# eMMC_TPM.net
KiCad netlist of a schematic drawn in Altium Designer
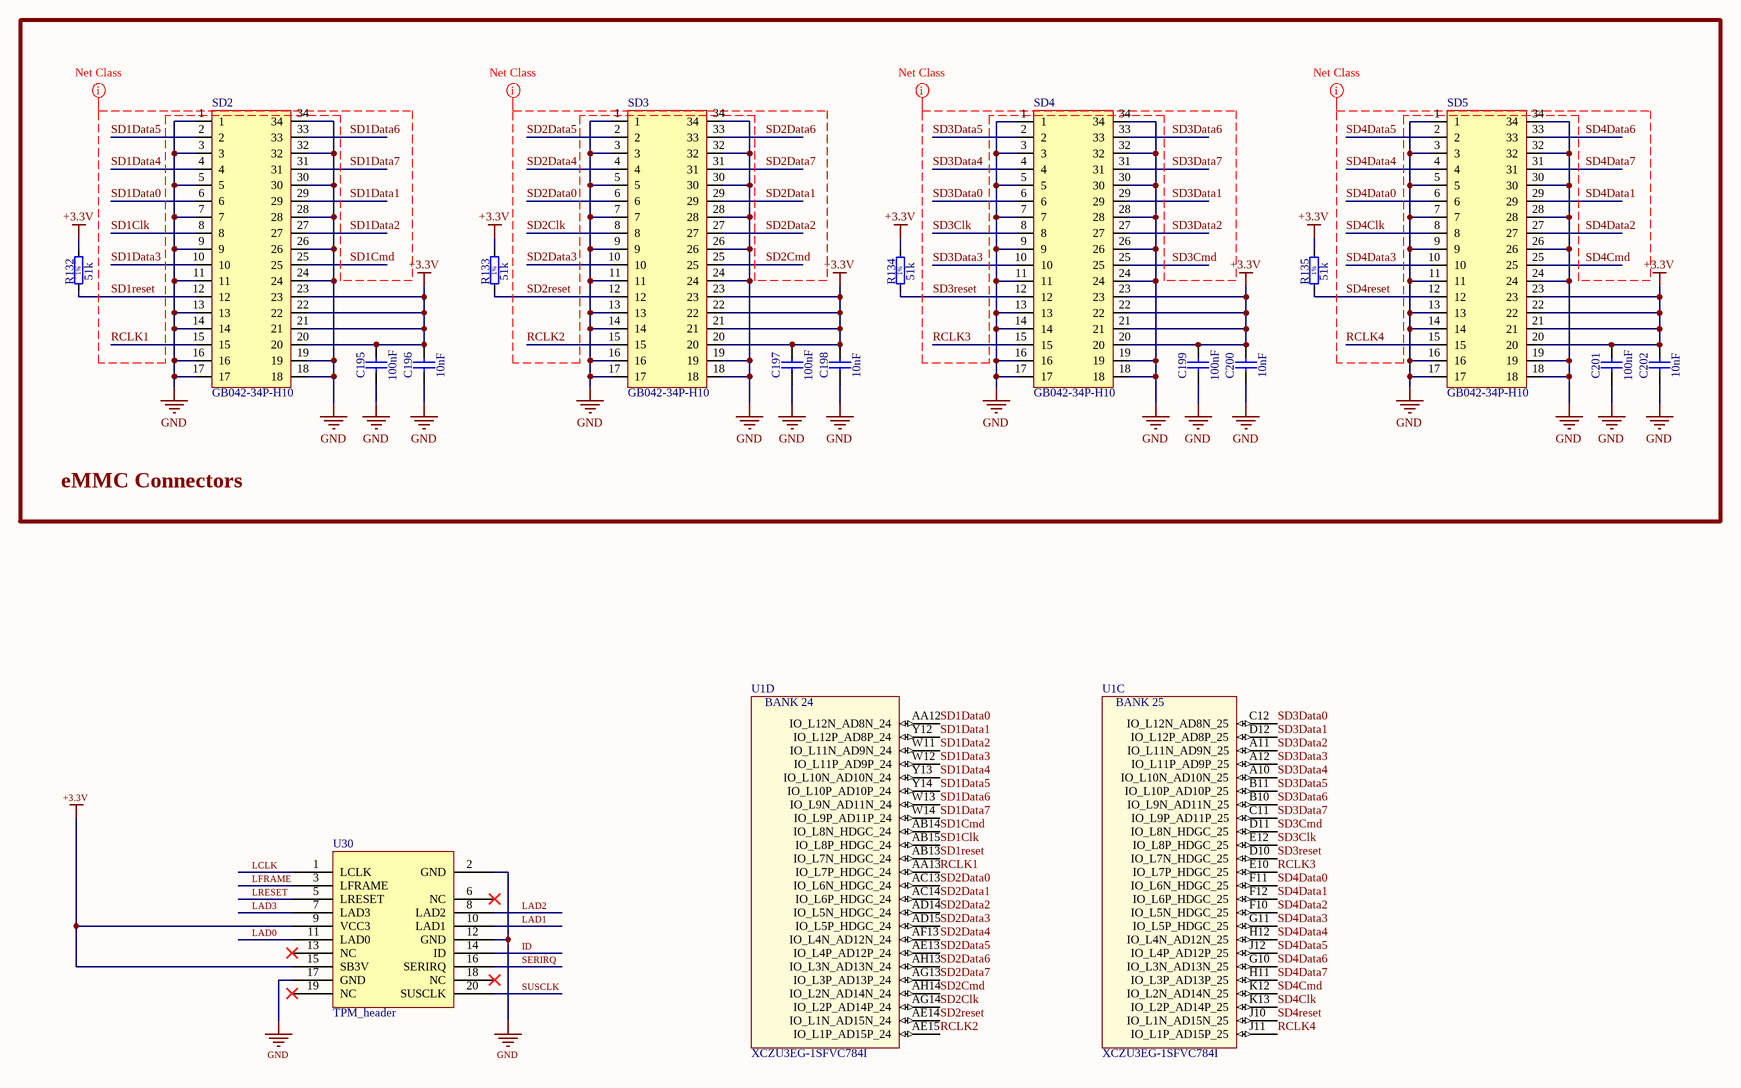
[diagram p0: eMMC_TPM.SchDoc]

(export (version "E")
  (design (tool "Eeschema 10.0.6"))
  (components
    (comp (ref "C195")
      (value "100nF")
      (footprint "Ultrascale_PcbLib:CAPC1608X87N")
      (description "Non-polarised capacitor")
      (fields
        (field (name "PART NUMBER") "CC0603_100NF_50V_10%_X7R")
        (field (name "VOLTAGE") "50V")
        (field (name "AUTHOR") "CERN DEM JLC")
      )
      (libsource (lib "Ultrascale_SchLib") (part "Capacitor - non polarized"))
    )
    (comp (ref "C196")
      (value "10nF")
      (footprint "Ultrascale_PcbLib:CAPC1608X87N")
      (description "Non-polarised capacitor")
      (fields
        (field (name "PART NUMBER") "CC0603_10NF_50V_10%_X7R")
        (field (name "VOLTAGE") "50V")
        (field (name "AUTHOR") "CERN DEM JLC")
      )
      (libsource (lib "Ultrascale_SchLib") (part "Capacitor - non polarized"))
    )
    (comp (ref "C197")
      (value "100nF")
      (footprint "Ultrascale_PcbLib:CAPC1608X87N")
      (description "Non-polarised capacitor")
      (fields
        (field (name "PART NUMBER") "CC0603_100NF_50V_10%_X7R")
        (field (name "VOLTAGE") "50V")
        (field (name "AUTHOR") "CERN DEM JLC")
      )
      (libsource (lib "Ultrascale_SchLib") (part "Capacitor - non polarized"))
    )
    (comp (ref "C198")
      (value "10nF")
      (footprint "Ultrascale_PcbLib:CAPC1608X87N")
      (description "Non-polarised capacitor")
      (fields
        (field (name "PART NUMBER") "CC0603_10NF_50V_10%_X7R")
        (field (name "VOLTAGE") "50V")
        (field (name "AUTHOR") "CERN DEM JLC")
      )
      (libsource (lib "Ultrascale_SchLib") (part "Capacitor - non polarized"))
    )
    (comp (ref "C199")
      (value "100nF")
      (footprint "Ultrascale_PcbLib:CAPC1608X87N")
      (description "Non-polarised capacitor")
      (fields
        (field (name "PART NUMBER") "CC0603_100NF_50V_10%_X7R")
        (field (name "VOLTAGE") "50V")
        (field (name "AUTHOR") "CERN DEM JLC")
      )
      (libsource (lib "Ultrascale_SchLib") (part "Capacitor - non polarized"))
    )
    (comp (ref "C200")
      (value "10nF")
      (footprint "Ultrascale_PcbLib:CAPC1608X87N")
      (description "Non-polarised capacitor")
      (fields
        (field (name "PART NUMBER") "CC0603_10NF_50V_10%_X7R")
        (field (name "VOLTAGE") "50V")
        (field (name "AUTHOR") "CERN DEM JLC")
      )
      (libsource (lib "Ultrascale_SchLib") (part "Capacitor - non polarized"))
    )
    (comp (ref "C201")
      (value "100nF")
      (footprint "Ultrascale_PcbLib:CAPC1608X87N")
      (description "Non-polarised capacitor")
      (fields
        (field (name "PART NUMBER") "CC0603_100NF_50V_10%_X7R")
        (field (name "VOLTAGE") "50V")
        (field (name "AUTHOR") "CERN DEM JLC")
      )
      (libsource (lib "Ultrascale_SchLib") (part "Capacitor - non polarized"))
    )
    (comp (ref "C202")
      (value "10nF")
      (footprint "Ultrascale_PcbLib:CAPC1608X87N")
      (description "Non-polarised capacitor")
      (fields
        (field (name "PART NUMBER") "CC0603_10NF_50V_10%_X7R")
        (field (name "VOLTAGE") "50V")
        (field (name "AUTHOR") "CERN DEM JLC")
      )
      (libsource (lib "Ultrascale_SchLib") (part "Capacitor - non polarized"))
    )
    (comp (ref "R132")
      (value "51k")
      (footprint "Ultrascale_PcbLib:RESC1608X55N")
      (description "Resistor - 1%")
      (fields
        (field (name "PART NUMBER") "R0603_51K_1%_0.1W_100PPM")
        (field (name "POWER") "0.1W")
        (field (name "AUTHOR") "CERN DEM JLC")
      )
      (libsource (lib "Ultrascale_SchLib") (part "Resistor - 1%"))
    )
    (comp (ref "R133")
      (value "51k")
      (footprint "Ultrascale_PcbLib:RESC1608X55N")
      (description "Resistor - 1%")
      (fields
        (field (name "PART NUMBER") "R0603_51K_1%_0.1W_100PPM")
        (field (name "POWER") "0.1W")
        (field (name "AUTHOR") "CERN DEM JLC")
      )
      (libsource (lib "Ultrascale_SchLib") (part "Resistor - 1%"))
    )
    (comp (ref "R134")
      (value "51k")
      (footprint "Ultrascale_PcbLib:RESC1608X55N")
      (description "Resistor - 1%")
      (fields
        (field (name "PART NUMBER") "R0603_51K_1%_0.1W_100PPM")
        (field (name "POWER") "0.1W")
        (field (name "AUTHOR") "CERN DEM JLC")
      )
      (libsource (lib "Ultrascale_SchLib") (part "Resistor - 1%"))
    )
    (comp (ref "R135")
      (value "51k")
      (footprint "Ultrascale_PcbLib:RESC1608X55N")
      (description "Resistor - 1%")
      (fields
        (field (name "PART NUMBER") "R0603_51K_1%_0.1W_100PPM")
        (field (name "POWER") "0.1W")
        (field (name "AUTHOR") "CERN DEM JLC")
      )
      (libsource (lib "Ultrascale_SchLib") (part "Resistor - 1%"))
    )
    (comp (ref "SD2")
      (value "GB042-34P-H10")
      (footprint "Ultrascale_PcbLib:GB042-34P-H10")
      (description "Connector, eMMC")
      (libsource (lib "Ultrascale_SchLib") (part "GB042-34P-H10"))
    )
    (comp (ref "SD3")
      (value "GB042-34P-H10")
      (footprint "Ultrascale_PcbLib:GB042-34P-H10")
      (description "Connector, eMMC")
      (libsource (lib "Ultrascale_SchLib") (part "GB042-34P-H10"))
    )
    (comp (ref "SD4")
      (value "GB042-34P-H10")
      (footprint "Ultrascale_PcbLib:GB042-34P-H10")
      (description "Connector, eMMC")
      (libsource (lib "Ultrascale_SchLib") (part "GB042-34P-H10"))
    )
    (comp (ref "SD5")
      (value "GB042-34P-H10")
      (footprint "Ultrascale_PcbLib:GB042-34P-H10")
      (description "Connector, eMMC")
      (libsource (lib "Ultrascale_SchLib") (part "GB042-34P-H10"))
    )
    (comp (ref "U1")
      (value "XCZU3EG-1SFVC784I")
      (footprint "BGA784x28")
      (description "IC FPGA 252 I/O 784FCBGA - XILINX ZYNQ ULTRASCALE+")
      (libsource (lib "Ultrascale_SchLib") (part "XCZU3EG-1SFVC784I"))
    )
    (comp (ref "U30")
      (value "TPM_header")
      (footprint "PIN HEADER 20POS")
      (description "GC-TPM-rev-20")
      (libsource (lib "Ultrascale_SchLib") (part "TPM_header"))
    )
  )
  (nets
    (net (code "1") (name "+3.3V") (class "Default")
      (node (ref "C195") (pin "2") (pinfunction "2_2") (pintype "passive"))
      (node (ref "C196") (pin "2") (pinfunction "2_2") (pintype "passive"))
      (node (ref "C197") (pin "2") (pinfunction "2_2") (pintype "passive"))
      (node (ref "C198") (pin "2") (pinfunction "2_2") (pintype "passive"))
      (node (ref "C199") (pin "2") (pinfunction "2_2") (pintype "passive"))
      (node (ref "C200") (pin "2") (pinfunction "2_2") (pintype "passive"))
      (node (ref "C201") (pin "2") (pinfunction "2_2") (pintype "passive"))
      (node (ref "C202") (pin "2") (pinfunction "2_2") (pintype "passive"))
      (node (ref "R132") (pin "2") (pinfunction "2_2") (pintype "passive"))
      (node (ref "R133") (pin "2") (pinfunction "2_2") (pintype "passive"))
      (node (ref "R134") (pin "2") (pinfunction "2_2") (pintype "passive"))
      (node (ref "R135") (pin "2") (pinfunction "2_2") (pintype "passive"))
      (node (ref "SD2") (pin "20") (pinfunction "20_20") (pintype "passive"))
      (node (ref "SD2") (pin "21") (pinfunction "21_21") (pintype "passive"))
      (node (ref "SD2") (pin "22") (pinfunction "22_22") (pintype "passive"))
      (node (ref "SD2") (pin "23") (pinfunction "23_23") (pintype "passive"))
      (node (ref "SD3") (pin "20") (pinfunction "20_20") (pintype "passive"))
      (node (ref "SD3") (pin "21") (pinfunction "21_21") (pintype "passive"))
      (node (ref "SD3") (pin "22") (pinfunction "22_22") (pintype "passive"))
      (node (ref "SD3") (pin "23") (pinfunction "23_23") (pintype "passive"))
      (node (ref "SD4") (pin "20") (pinfunction "20_20") (pintype "passive"))
      (node (ref "SD4") (pin "21") (pinfunction "21_21") (pintype "passive"))
      (node (ref "SD4") (pin "22") (pinfunction "22_22") (pintype "passive"))
      (node (ref "SD4") (pin "23") (pinfunction "23_23") (pintype "passive"))
      (node (ref "SD5") (pin "20") (pinfunction "20_20") (pintype "passive"))
      (node (ref "SD5") (pin "21") (pinfunction "21_21") (pintype "passive"))
      (node (ref "SD5") (pin "22") (pinfunction "22_22") (pintype "passive"))
      (node (ref "SD5") (pin "23") (pinfunction "23_23") (pintype "passive"))
      (node (ref "U30") (pin "15") (pinfunction "SB3V_15") (pintype "power_in"))
      (node (ref "U30") (pin "9") (pinfunction "VCC3_9") (pintype "power_in"))
    )
    (net (code "2") (name "/ID") (class "Default")
      (node (ref "U30") (pin "14") (pinfunction "ID_14") (pintype "power_in"))
    )
    (net (code "3") (name "/LAD0") (class "Default")
      (node (ref "U30") (pin "11") (pinfunction "LAD0_11") (pintype "power_in"))
    )
    (net (code "4") (name "/LAD1") (class "Default")
      (node (ref "U30") (pin "10") (pinfunction "LAD1_10") (pintype "power_in"))
    )
    (net (code "5") (name "/LAD2") (class "Default")
      (node (ref "U30") (pin "8") (pinfunction "LAD2_8") (pintype "power_in"))
    )
    (net (code "6") (name "/LAD3") (class "Default")
      (node (ref "U30") (pin "7") (pinfunction "LAD3_7") (pintype "power_in"))
    )
    (net (code "7") (name "/LCLK") (class "Default")
      (node (ref "U30") (pin "1") (pinfunction "LCLK_1") (pintype "power_in"))
    )
    (net (code "8") (name "/LFRAME") (class "Default")
      (node (ref "U30") (pin "3") (pinfunction "LFRAME_3") (pintype "power_in"))
    )
    (net (code "9") (name "/LRESET") (class "Default")
      (node (ref "U30") (pin "5") (pinfunction "LRESET_5") (pintype "power_in"))
    )
    (net (code "10") (name "/RCLK1") (class "Default")
      (node (ref "SD2") (pin "15") (pinfunction "15_15") (pintype "passive"))
      (node (ref "U1") (pin "AA13") (pinfunction "IO_L7P_HDGC_24_AA13") (pintype "bidirectional"))
    )
    (net (code "11") (name "/RCLK2") (class "Default")
      (node (ref "SD3") (pin "15") (pinfunction "15_15") (pintype "passive"))
      (node (ref "U1") (pin "AE15") (pinfunction "IO_L1P_AD15P_24_AE15") (pintype "bidirectional"))
    )
    (net (code "12") (name "/RCLK3") (class "Default")
      (node (ref "SD4") (pin "15") (pinfunction "15_15") (pintype "passive"))
      (node (ref "U1") (pin "E10") (pinfunction "IO_L7P_HDGC_25_E10") (pintype "bidirectional"))
    )
    (net (code "13") (name "/RCLK4") (class "Default")
      (node (ref "SD5") (pin "15") (pinfunction "15_15") (pintype "passive"))
      (node (ref "U1") (pin "J11") (pinfunction "IO_L1P_AD15P_25_J11") (pintype "bidirectional"))
    )
    (net (code "14") (name "/SD1Clk") (class "Default")
      (node (ref "SD2") (pin "8") (pinfunction "8_8") (pintype "passive"))
      (node (ref "U1") (pin "AB15") (pinfunction "IO_L8P_HDGC_24_AB15") (pintype "bidirectional"))
    )
    (net (code "15") (name "/SD1Cmd") (class "Default")
      (node (ref "SD2") (pin "25") (pinfunction "25_25") (pintype "passive"))
      (node (ref "U1") (pin "AB14") (pinfunction "IO_L8N_HDGC_24_AB14") (pintype "bidirectional"))
    )
    (net (code "16") (name "/SD1Data0") (class "Default")
      (node (ref "SD2") (pin "6") (pinfunction "6_6") (pintype "passive"))
      (node (ref "U1") (pin "AA12") (pinfunction "IO_L12N_AD8N_24_AA12") (pintype "bidirectional"))
    )
    (net (code "17") (name "/SD1Data1") (class "Default")
      (node (ref "SD2") (pin "29") (pinfunction "29_29") (pintype "passive"))
      (node (ref "U1") (pin "Y12") (pinfunction "IO_L12P_AD8P_24_Y12") (pintype "bidirectional"))
    )
    (net (code "18") (name "/SD1Data2") (class "Default")
      (node (ref "SD2") (pin "27") (pinfunction "27_27") (pintype "passive"))
      (node (ref "U1") (pin "W11") (pinfunction "IO_L11N_AD9N_24_W11") (pintype "bidirectional"))
    )
    (net (code "19") (name "/SD1Data3") (class "Default")
      (node (ref "SD2") (pin "10") (pinfunction "10_10") (pintype "passive"))
      (node (ref "U1") (pin "W12") (pinfunction "IO_L11P_AD9P_24_W12") (pintype "bidirectional"))
    )
    (net (code "20") (name "/SD1Data4") (class "Default")
      (node (ref "SD2") (pin "4") (pinfunction "4_4") (pintype "passive"))
      (node (ref "U1") (pin "Y13") (pinfunction "IO_L10N_AD10N_24_Y13") (pintype "bidirectional"))
    )
    (net (code "21") (name "/SD1Data5") (class "Default")
      (node (ref "SD2") (pin "2") (pinfunction "2_2") (pintype "passive"))
      (node (ref "U1") (pin "Y14") (pinfunction "IO_L10P_AD10P_24_Y14") (pintype "bidirectional"))
    )
    (net (code "22") (name "/SD1Data6") (class "Default")
      (node (ref "SD2") (pin "33") (pinfunction "33_33") (pintype "passive"))
      (node (ref "U1") (pin "W13") (pinfunction "IO_L9N_AD11N_24_W13") (pintype "bidirectional"))
    )
    (net (code "23") (name "/SD1Data7") (class "Default")
      (node (ref "SD2") (pin "31") (pinfunction "31_31") (pintype "passive"))
      (node (ref "U1") (pin "W14") (pinfunction "IO_L9P_AD11P_24_W14") (pintype "bidirectional"))
    )
    (net (code "24") (name "/SD1reset") (class "Default")
      (node (ref "R132") (pin "1") (pinfunction "1_1") (pintype "passive"))
      (node (ref "SD2") (pin "12") (pinfunction "12_12") (pintype "passive"))
      (node (ref "U1") (pin "AB13") (pinfunction "IO_L7N_HDGC_24_AB13") (pintype "bidirectional"))
    )
    (net (code "25") (name "/SD2Clk") (class "Default")
      (node (ref "SD3") (pin "8") (pinfunction "8_8") (pintype "passive"))
      (node (ref "U1") (pin "AG14") (pinfunction "IO_L2P_AD14P_24_AG14") (pintype "bidirectional"))
    )
    (net (code "26") (name "/SD2Cmd") (class "Default")
      (node (ref "SD3") (pin "25") (pinfunction "25_25") (pintype "passive"))
      (node (ref "U1") (pin "AH14") (pinfunction "IO_L2N_AD14N_24_AH14") (pintype "bidirectional"))
    )
    (net (code "27") (name "/SD2Data0") (class "Default")
      (node (ref "SD3") (pin "6") (pinfunction "6_6") (pintype "passive"))
      (node (ref "U1") (pin "AC13") (pinfunction "IO_L6N_HDGC_24_AC13") (pintype "bidirectional"))
    )
    (net (code "28") (name "/SD2Data1") (class "Default")
      (node (ref "SD3") (pin "29") (pinfunction "29_29") (pintype "passive"))
      (node (ref "U1") (pin "AC14") (pinfunction "IO_L6P_HDGC_24_AC14") (pintype "bidirectional"))
    )
    (net (code "29") (name "/SD2Data2") (class "Default")
      (node (ref "SD3") (pin "27") (pinfunction "27_27") (pintype "passive"))
      (node (ref "U1") (pin "AD14") (pinfunction "IO_L5N_HDGC_24_AD14") (pintype "bidirectional"))
    )
    (net (code "30") (name "/SD2Data3") (class "Default")
      (node (ref "SD3") (pin "10") (pinfunction "10_10") (pintype "passive"))
      (node (ref "U1") (pin "AD15") (pinfunction "IO_L5P_HDGC_24_AD15") (pintype "bidirectional"))
    )
    (net (code "31") (name "/SD2Data4") (class "Default")
      (node (ref "SD3") (pin "4") (pinfunction "4_4") (pintype "passive"))
      (node (ref "U1") (pin "AF13") (pinfunction "IO_L4N_AD12N_24_AF13") (pintype "bidirectional"))
    )
    (net (code "32") (name "/SD2Data5") (class "Default")
      (node (ref "SD3") (pin "2") (pinfunction "2_2") (pintype "passive"))
      (node (ref "U1") (pin "AE13") (pinfunction "IO_L4P_AD12P_24_AE13") (pintype "bidirectional"))
    )
    (net (code "33") (name "/SD2Data6") (class "Default")
      (node (ref "SD3") (pin "33") (pinfunction "33_33") (pintype "passive"))
      (node (ref "U1") (pin "AH13") (pinfunction "IO_L3N_AD13N_24_AH13") (pintype "bidirectional"))
    )
    (net (code "34") (name "/SD2Data7") (class "Default")
      (node (ref "SD3") (pin "31") (pinfunction "31_31") (pintype "passive"))
      (node (ref "U1") (pin "AG13") (pinfunction "IO_L3P_AD13P_24_AG13") (pintype "bidirectional"))
    )
    (net (code "35") (name "/SD2reset") (class "Default")
      (node (ref "R133") (pin "1") (pinfunction "1_1") (pintype "passive"))
      (node (ref "SD3") (pin "12") (pinfunction "12_12") (pintype "passive"))
      (node (ref "U1") (pin "AE14") (pinfunction "IO_L1N_AD15N_24_AE14") (pintype "bidirectional"))
    )
    (net (code "36") (name "/SD3Clk") (class "Default")
      (node (ref "SD4") (pin "8") (pinfunction "8_8") (pintype "passive"))
      (node (ref "U1") (pin "E12") (pinfunction "IO_L8P_HDGC_25_E12") (pintype "bidirectional"))
    )
    (net (code "37") (name "/SD3Cmd") (class "Default")
      (node (ref "SD4") (pin "25") (pinfunction "25_25") (pintype "passive"))
      (node (ref "U1") (pin "D11") (pinfunction "IO_L8N_HDGC_25_D11") (pintype "bidirectional"))
    )
    (net (code "38") (name "/SD3Data0") (class "Default")
      (node (ref "SD4") (pin "6") (pinfunction "6_6") (pintype "passive"))
      (node (ref "U1") (pin "C12") (pinfunction "IO_L12N_AD8N_25_C12") (pintype "bidirectional"))
    )
    (net (code "39") (name "/SD3Data1") (class "Default")
      (node (ref "SD4") (pin "29") (pinfunction "29_29") (pintype "passive"))
      (node (ref "U1") (pin "D12") (pinfunction "IO_L12P_AD8P_25_D12") (pintype "bidirectional"))
    )
    (net (code "40") (name "/SD3Data2") (class "Default")
      (node (ref "SD4") (pin "27") (pinfunction "27_27") (pintype "passive"))
      (node (ref "U1") (pin "A11") (pinfunction "IO_L11N_AD9N_25_A11") (pintype "bidirectional"))
    )
    (net (code "41") (name "/SD3Data3") (class "Default")
      (node (ref "SD4") (pin "10") (pinfunction "10_10") (pintype "passive"))
      (node (ref "U1") (pin "A12") (pinfunction "IO_L11P_AD9P_25_A12") (pintype "bidirectional"))
    )
    (net (code "42") (name "/SD3Data4") (class "Default")
      (node (ref "SD4") (pin "4") (pinfunction "4_4") (pintype "passive"))
      (node (ref "U1") (pin "A10") (pinfunction "IO_L10N_AD10N_25_A10") (pintype "bidirectional"))
    )
    (net (code "43") (name "/SD3Data5") (class "Default")
      (node (ref "SD4") (pin "2") (pinfunction "2_2") (pintype "passive"))
      (node (ref "U1") (pin "B11") (pinfunction "IO_L10P_AD10P_25_B11") (pintype "bidirectional"))
    )
    (net (code "44") (name "/SD3Data6") (class "Default")
      (node (ref "SD4") (pin "33") (pinfunction "33_33") (pintype "passive"))
      (node (ref "U1") (pin "B10") (pinfunction "IO_L9N_AD11N_25_B10") (pintype "bidirectional"))
    )
    (net (code "45") (name "/SD3Data7") (class "Default")
      (node (ref "SD4") (pin "31") (pinfunction "31_31") (pintype "passive"))
      (node (ref "U1") (pin "C11") (pinfunction "IO_L9P_AD11P_25_C11") (pintype "bidirectional"))
    )
    (net (code "46") (name "/SD3reset") (class "Default")
      (node (ref "R134") (pin "1") (pinfunction "1_1") (pintype "passive"))
      (node (ref "SD4") (pin "12") (pinfunction "12_12") (pintype "passive"))
      (node (ref "U1") (pin "D10") (pinfunction "IO_L7N_HDGC_25_D10") (pintype "bidirectional"))
    )
    (net (code "47") (name "/SD4Clk") (class "Default")
      (node (ref "SD5") (pin "8") (pinfunction "8_8") (pintype "passive"))
      (node (ref "U1") (pin "K13") (pinfunction "IO_L2P_AD14P_25_K13") (pintype "bidirectional"))
    )
    (net (code "48") (name "/SD4Cmd") (class "Default")
      (node (ref "SD5") (pin "25") (pinfunction "25_25") (pintype "passive"))
      (node (ref "U1") (pin "K12") (pinfunction "IO_L2N_AD14N_25_K12") (pintype "bidirectional"))
    )
    (net (code "49") (name "/SD4Data0") (class "Default")
      (node (ref "SD5") (pin "6") (pinfunction "6_6") (pintype "passive"))
      (node (ref "U1") (pin "F11") (pinfunction "IO_L6N_HDGC_25_F11") (pintype "bidirectional"))
    )
    (net (code "50") (name "/SD4Data1") (class "Default")
      (node (ref "SD5") (pin "29") (pinfunction "29_29") (pintype "passive"))
      (node (ref "U1") (pin "F12") (pinfunction "IO_L6P_HDGC_25_F12") (pintype "bidirectional"))
    )
    (net (code "51") (name "/SD4Data2") (class "Default")
      (node (ref "SD5") (pin "27") (pinfunction "27_27") (pintype "passive"))
      (node (ref "U1") (pin "F10") (pinfunction "IO_L5N_HDGC_25_F10") (pintype "bidirectional"))
    )
    (net (code "52") (name "/SD4Data3") (class "Default")
      (node (ref "SD5") (pin "10") (pinfunction "10_10") (pintype "passive"))
      (node (ref "U1") (pin "G11") (pinfunction "IO_L5P_HDGC_25_G11") (pintype "bidirectional"))
    )
    (net (code "53") (name "/SD4Data4") (class "Default")
      (node (ref "SD5") (pin "4") (pinfunction "4_4") (pintype "passive"))
      (node (ref "U1") (pin "H12") (pinfunction "IO_L4N_AD12N_25_H12") (pintype "bidirectional"))
    )
    (net (code "54") (name "/SD4Data5") (class "Default")
      (node (ref "SD5") (pin "2") (pinfunction "2_2") (pintype "passive"))
      (node (ref "U1") (pin "J12") (pinfunction "IO_L4P_AD12P_25_J12") (pintype "bidirectional"))
    )
    (net (code "55") (name "/SD4Data6") (class "Default")
      (node (ref "SD5") (pin "33") (pinfunction "33_33") (pintype "passive"))
      (node (ref "U1") (pin "G10") (pinfunction "IO_L3N_AD13N_25_G10") (pintype "bidirectional"))
    )
    (net (code "56") (name "/SD4Data7") (class "Default")
      (node (ref "SD5") (pin "31") (pinfunction "31_31") (pintype "passive"))
      (node (ref "U1") (pin "H11") (pinfunction "IO_L3P_AD13P_25_H11") (pintype "bidirectional"))
    )
    (net (code "57") (name "/SD4reset") (class "Default")
      (node (ref "R135") (pin "1") (pinfunction "1_1") (pintype "passive"))
      (node (ref "SD5") (pin "12") (pinfunction "12_12") (pintype "passive"))
      (node (ref "U1") (pin "J10") (pinfunction "IO_L1N_AD15N_25_J10") (pintype "bidirectional"))
    )
    (net (code "58") (name "/SERIRQ") (class "Default")
      (node (ref "U30") (pin "16") (pinfunction "SERIRQ_16") (pintype "power_in"))
    )
    (net (code "59") (name "/SUSCLK") (class "Default")
      (node (ref "U30") (pin "20") (pinfunction "SUSCLK_20") (pintype "power_in"))
    )
    (net (code "60") (name "GND") (class "Default")
      (node (ref "C195") (pin "1") (pinfunction "1_1") (pintype "passive"))
      (node (ref "C196") (pin "1") (pinfunction "1_1") (pintype "passive"))
      (node (ref "C197") (pin "1") (pinfunction "1_1") (pintype "passive"))
      (node (ref "C198") (pin "1") (pinfunction "1_1") (pintype "passive"))
      (node (ref "C199") (pin "1") (pinfunction "1_1") (pintype "passive"))
      (node (ref "C200") (pin "1") (pinfunction "1_1") (pintype "passive"))
      (node (ref "C201") (pin "1") (pinfunction "1_1") (pintype "passive"))
      (node (ref "C202") (pin "1") (pinfunction "1_1") (pintype "passive"))
      (node (ref "SD2") (pin "1") (pinfunction "1_1") (pintype "passive"))
      (node (ref "SD2") (pin "11") (pinfunction "11_11") (pintype "passive"))
      (node (ref "SD2") (pin "13") (pinfunction "13_13") (pintype "passive"))
      (node (ref "SD2") (pin "14") (pinfunction "14_14") (pintype "passive"))
      (node (ref "SD2") (pin "16") (pinfunction "16_16") (pintype "passive"))
      (node (ref "SD2") (pin "17") (pinfunction "17_17") (pintype "passive"))
      (node (ref "SD2") (pin "18") (pinfunction "18_18") (pintype "passive"))
      (node (ref "SD2") (pin "19") (pinfunction "19_19") (pintype "passive"))
      (node (ref "SD2") (pin "24") (pinfunction "24_24") (pintype "passive"))
      (node (ref "SD2") (pin "26") (pinfunction "26_26") (pintype "passive"))
      (node (ref "SD2") (pin "28") (pinfunction "28_28") (pintype "passive"))
      (node (ref "SD2") (pin "3") (pinfunction "3_3") (pintype "passive"))
      (node (ref "SD2") (pin "30") (pinfunction "30_30") (pintype "passive"))
      (node (ref "SD2") (pin "32") (pinfunction "32_32") (pintype "passive"))
      (node (ref "SD2") (pin "34") (pinfunction "34_34") (pintype "passive"))
      (node (ref "SD2") (pin "5") (pinfunction "5_5") (pintype "passive"))
      (node (ref "SD2") (pin "7") (pinfunction "7_7") (pintype "passive"))
      (node (ref "SD2") (pin "9") (pinfunction "9_9") (pintype "passive"))
      (node (ref "SD3") (pin "1") (pinfunction "1_1") (pintype "passive"))
      (node (ref "SD3") (pin "11") (pinfunction "11_11") (pintype "passive"))
      (node (ref "SD3") (pin "13") (pinfunction "13_13") (pintype "passive"))
      (node (ref "SD3") (pin "14") (pinfunction "14_14") (pintype "passive"))
      (node (ref "SD3") (pin "16") (pinfunction "16_16") (pintype "passive"))
      (node (ref "SD3") (pin "17") (pinfunction "17_17") (pintype "passive"))
      (node (ref "SD3") (pin "18") (pinfunction "18_18") (pintype "passive"))
      (node (ref "SD3") (pin "19") (pinfunction "19_19") (pintype "passive"))
      (node (ref "SD3") (pin "24") (pinfunction "24_24") (pintype "passive"))
      (node (ref "SD3") (pin "26") (pinfunction "26_26") (pintype "passive"))
      (node (ref "SD3") (pin "28") (pinfunction "28_28") (pintype "passive"))
      (node (ref "SD3") (pin "3") (pinfunction "3_3") (pintype "passive"))
      (node (ref "SD3") (pin "30") (pinfunction "30_30") (pintype "passive"))
      (node (ref "SD3") (pin "32") (pinfunction "32_32") (pintype "passive"))
      (node (ref "SD3") (pin "34") (pinfunction "34_34") (pintype "passive"))
      (node (ref "SD3") (pin "5") (pinfunction "5_5") (pintype "passive"))
      (node (ref "SD3") (pin "7") (pinfunction "7_7") (pintype "passive"))
      (node (ref "SD3") (pin "9") (pinfunction "9_9") (pintype "passive"))
      (node (ref "SD4") (pin "1") (pinfunction "1_1") (pintype "passive"))
      (node (ref "SD4") (pin "11") (pinfunction "11_11") (pintype "passive"))
      (node (ref "SD4") (pin "13") (pinfunction "13_13") (pintype "passive"))
      (node (ref "SD4") (pin "14") (pinfunction "14_14") (pintype "passive"))
      (node (ref "SD4") (pin "16") (pinfunction "16_16") (pintype "passive"))
      (node (ref "SD4") (pin "17") (pinfunction "17_17") (pintype "passive"))
      (node (ref "SD4") (pin "18") (pinfunction "18_18") (pintype "passive"))
      (node (ref "SD4") (pin "19") (pinfunction "19_19") (pintype "passive"))
      (node (ref "SD4") (pin "24") (pinfunction "24_24") (pintype "passive"))
      (node (ref "SD4") (pin "26") (pinfunction "26_26") (pintype "passive"))
      (node (ref "SD4") (pin "28") (pinfunction "28_28") (pintype "passive"))
      (node (ref "SD4") (pin "3") (pinfunction "3_3") (pintype "passive"))
      (node (ref "SD4") (pin "30") (pinfunction "30_30") (pintype "passive"))
      (node (ref "SD4") (pin "32") (pinfunction "32_32") (pintype "passive"))
      (node (ref "SD4") (pin "34") (pinfunction "34_34") (pintype "passive"))
      (node (ref "SD4") (pin "5") (pinfunction "5_5") (pintype "passive"))
      (node (ref "SD4") (pin "7") (pinfunction "7_7") (pintype "passive"))
      (node (ref "SD4") (pin "9") (pinfunction "9_9") (pintype "passive"))
      (node (ref "SD5") (pin "1") (pinfunction "1_1") (pintype "passive"))
      (node (ref "SD5") (pin "11") (pinfunction "11_11") (pintype "passive"))
      (node (ref "SD5") (pin "13") (pinfunction "13_13") (pintype "passive"))
      (node (ref "SD5") (pin "14") (pinfunction "14_14") (pintype "passive"))
      (node (ref "SD5") (pin "16") (pinfunction "16_16") (pintype "passive"))
      (node (ref "SD5") (pin "17") (pinfunction "17_17") (pintype "passive"))
      (node (ref "SD5") (pin "18") (pinfunction "18_18") (pintype "passive"))
      (node (ref "SD5") (pin "19") (pinfunction "19_19") (pintype "passive"))
      (node (ref "SD5") (pin "24") (pinfunction "24_24") (pintype "passive"))
      (node (ref "SD5") (pin "26") (pinfunction "26_26") (pintype "passive"))
      (node (ref "SD5") (pin "28") (pinfunction "28_28") (pintype "passive"))
      (node (ref "SD5") (pin "3") (pinfunction "3_3") (pintype "passive"))
      (node (ref "SD5") (pin "30") (pinfunction "30_30") (pintype "passive"))
      (node (ref "SD5") (pin "32") (pinfunction "32_32") (pintype "passive"))
      (node (ref "SD5") (pin "34") (pinfunction "34_34") (pintype "passive"))
      (node (ref "SD5") (pin "5") (pinfunction "5_5") (pintype "passive"))
      (node (ref "SD5") (pin "7") (pinfunction "7_7") (pintype "passive"))
      (node (ref "SD5") (pin "9") (pinfunction "9_9") (pintype "passive"))
      (node (ref "U30") (pin "12") (pinfunction "GND_12") (pintype "power_in"))
      (node (ref "U30") (pin "17") (pinfunction "GND_17") (pintype "power_in"))
      (node (ref "U30") (pin "2") (pinfunction "GND_2") (pintype "power_in"))
    )
    (net (code "61") (name "unconnected-(U30-NC-Pad6)") (class "Default")
      (node (ref "U30") (pin "6") (pinfunction "NC_6") (pintype "power_in+no_connect"))
    )
    (net (code "62") (name "unconnected-(U30-NC-Pad13)") (class "Default")
      (node (ref "U30") (pin "13") (pinfunction "NC_13") (pintype "power_in+no_connect"))
    )
    (net (code "63") (name "unconnected-(U30-NC-Pad18)") (class "Default")
      (node (ref "U30") (pin "18") (pinfunction "NC_18") (pintype "power_in+no_connect"))
    )
    (net (code "64") (name "unconnected-(U30-NC-Pad19)") (class "Default")
      (node (ref "U30") (pin "19") (pinfunction "NC_19") (pintype "power_in+no_connect"))
    )
  )
)
